# SCH_FARM_2023-08-20.net
KiCad netlist of a schematic drawn in EasyEDA
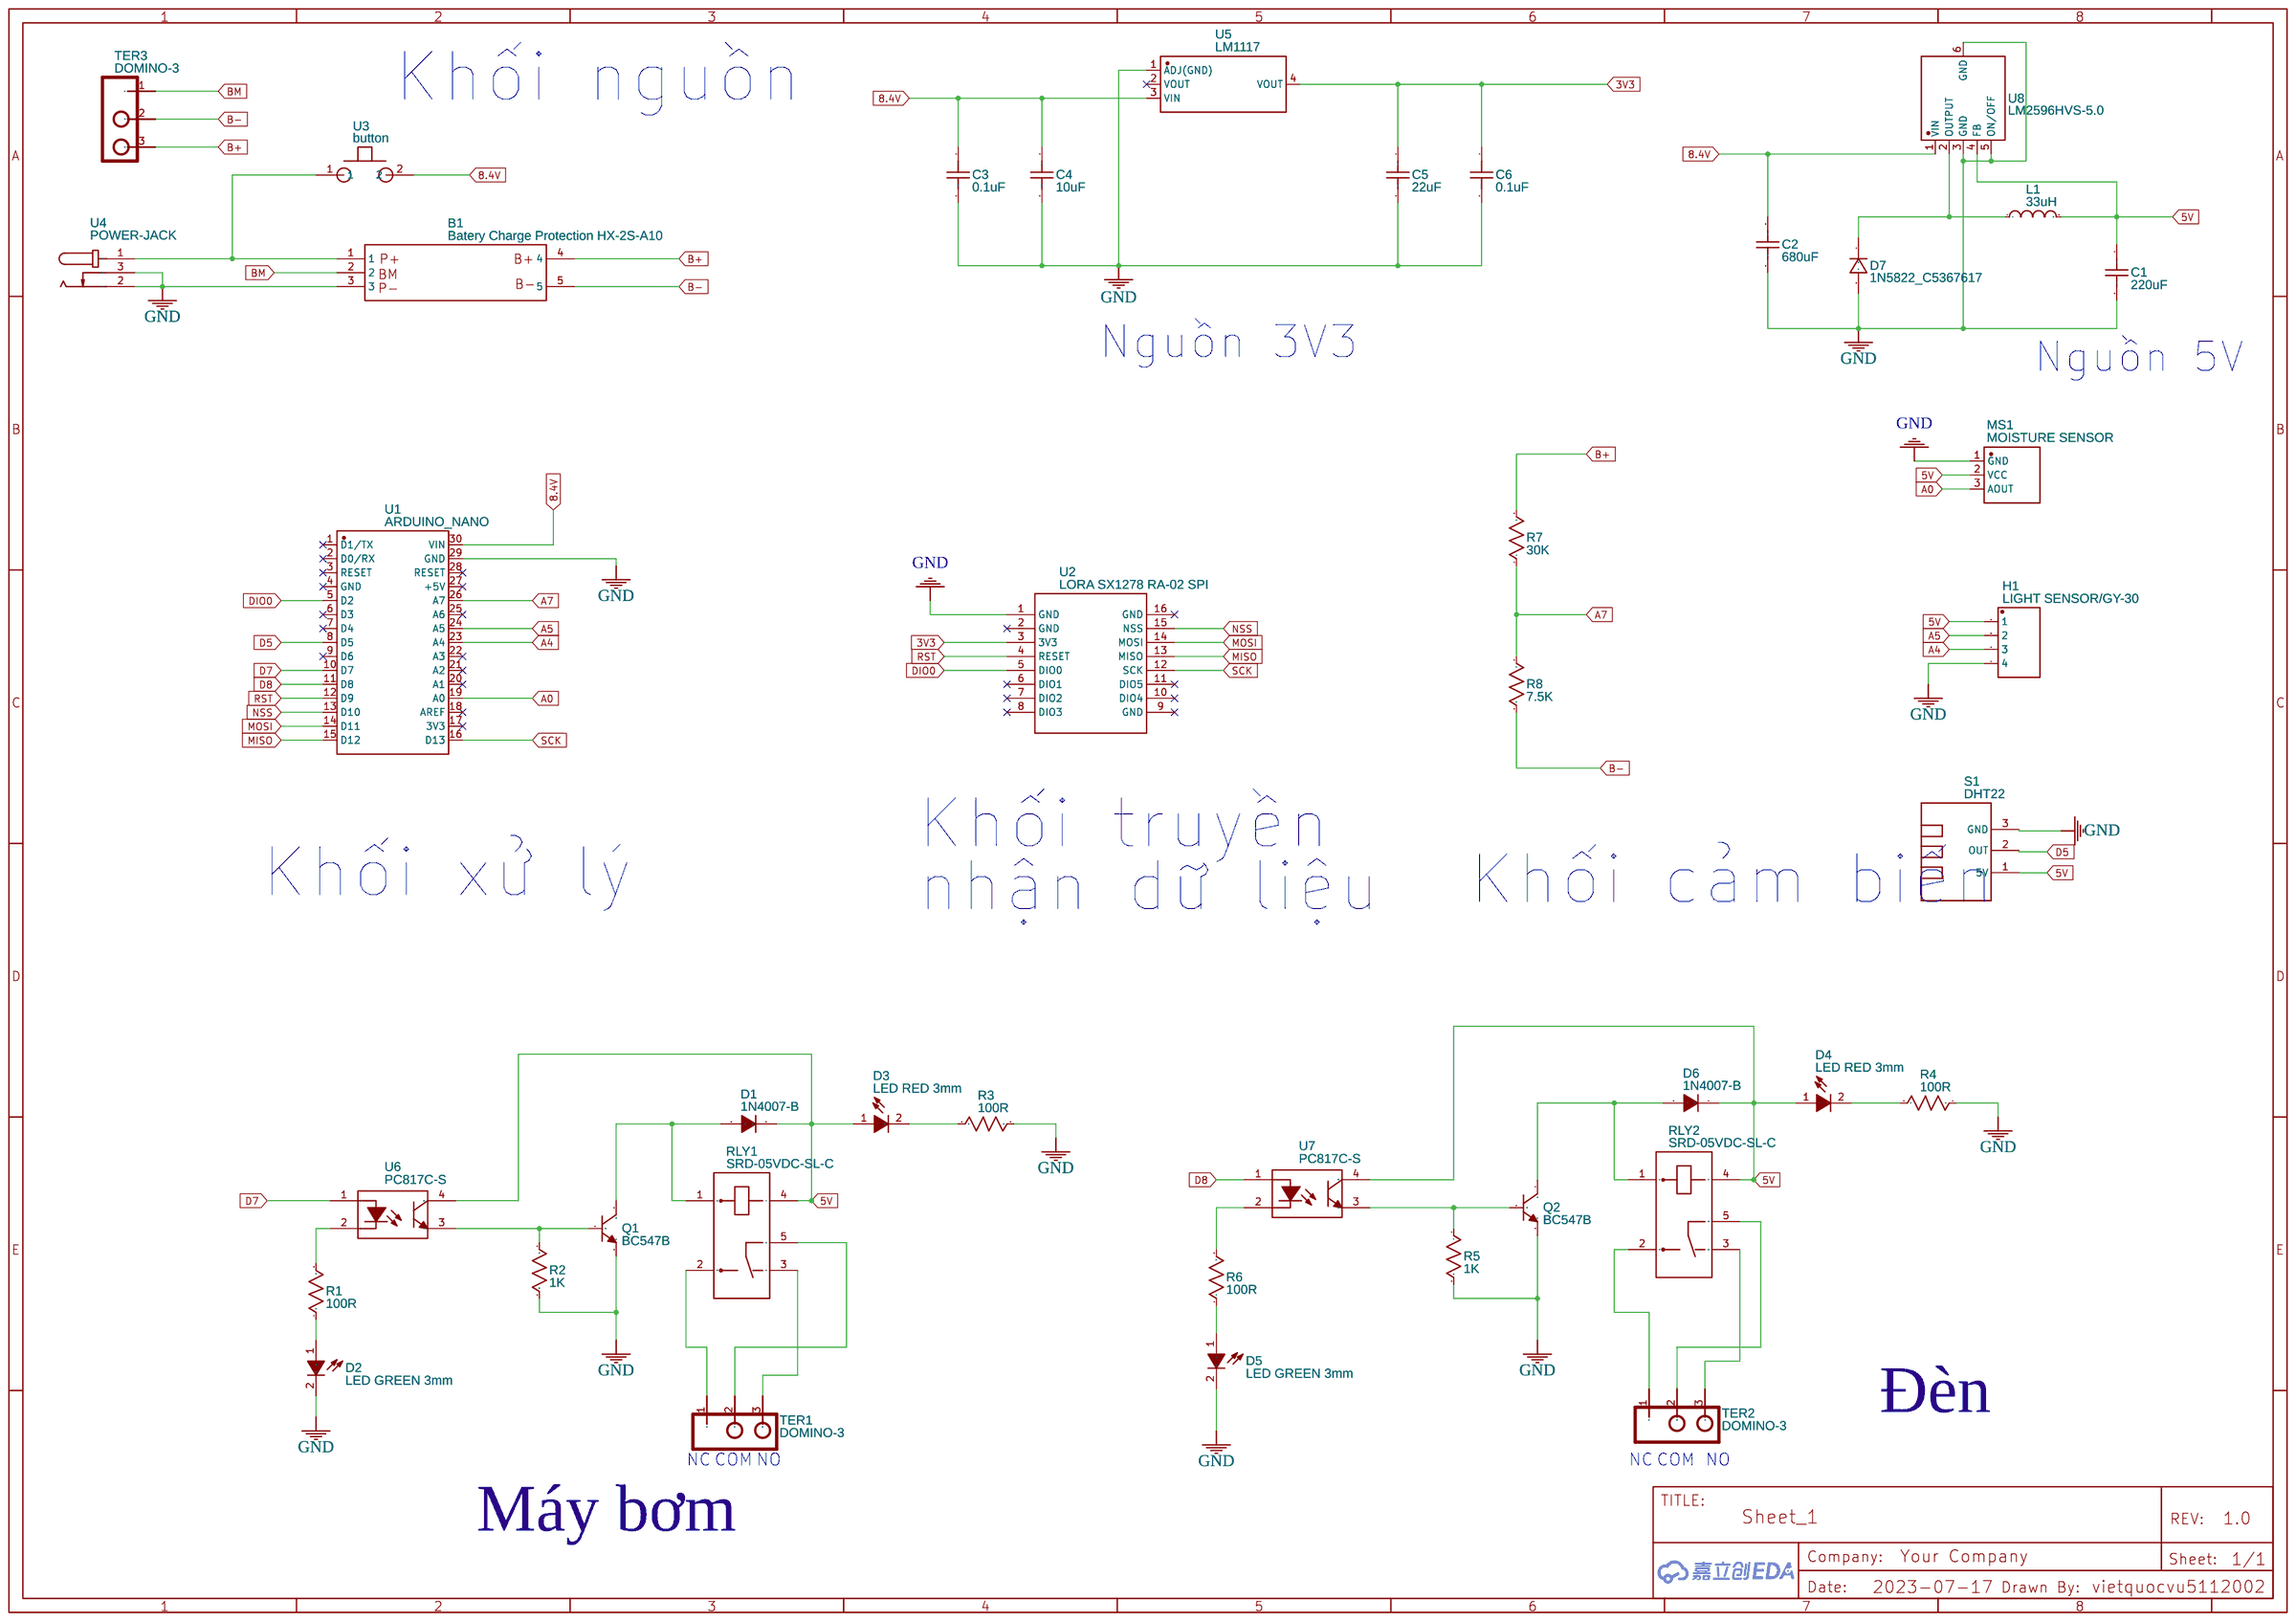
[diagram p0: schematic sheet]

(export (version "E")
  (design (tool "Eeschema 10.0.6"))
  (components
    (comp (ref "B1")
      (value "Batery Charge Protection HX-2S-A10")
      (fields (field (name "BOM_Manufacturer Part") "HX-2S-A10"))
      (libsource (lib "") (part "Batery Charge Protection HX-2S-A10"))
    )
    (comp (ref "C1") (value "220uF") (libsource (lib "") (part "C_0603_US")))
    (comp (ref "C2") (value "680uF") (libsource (lib "") (part "C_0603_US")))
    (comp (ref "C3") (value "0.1uF") (libsource (lib "") (part "C_0603_US")))
    (comp (ref "C4") (value "10uF") (libsource (lib "") (part "C_0603_US")))
    (comp (ref "C5") (value "22uF") (libsource (lib "") (part "C_0603_US")))
    (comp (ref "C6") (value "0.1uF") (libsource (lib "") (part "C_0603_US")))
    (comp (ref "D1")
      (value "1N4007-B")
      (fields (field (name "BOM_Supplier Part") "C526198"))
      (libsource (lib "") (part "1N4007-B"))
    )
    (comp (ref "D2")
      (value "LED GREEN 3mm")
      (fields (field (name "BOM_Manufacturer Part") "5600") (field (name "BOM_Supplier Part") "L20325-ND"))
      (libsource (lib "") (part "3mm Green TH LED 5600_1"))
    )
    (comp (ref "D3")
      (value "LED RED 3mm")
      (fields (field (name "BOM_Manufacturer Part") "5600") (field (name "BOM_Supplier Part") "L20325-ND"))
      (libsource (lib "") (part "3mm Green TH LED 5600"))
    )
    (comp (ref "D4")
      (value "LED RED 3mm")
      (fields (field (name "BOM_Manufacturer Part") "5600") (field (name "BOM_Supplier Part") "L20325-ND"))
      (libsource (lib "") (part "3mm Green TH LED 5600"))
    )
    (comp (ref "D5")
      (value "LED GREEN 3mm")
      (fields (field (name "BOM_Manufacturer Part") "5600") (field (name "BOM_Supplier Part") "L20325-ND"))
      (libsource (lib "") (part "3mm Green TH LED 5600_1"))
    )
    (comp (ref "D6")
      (value "1N4007-B")
      (fields (field (name "BOM_Supplier Part") "C526198"))
      (libsource (lib "") (part "1N4007-B"))
    )
    (comp (ref "D7")
      (value "1N5822_C5367617")
      (fields (field (name "BOM_Manufacturer Part") "1N5822") (field (name "BOM_Supplier Part") "C5367617"))
      (libsource (lib "") (part "1N5822_C5367617"))
    )
    (comp (ref "H1")
      (value "LIGHT SENSOR/GY-30")
      (fields
        (field (name "BOM_Manufacturer Part") "B-2100S04P-A110")
        (field (name "BOM_Supplier Part") "C124378")
      )
      (libsource (lib "") (part "Header-Male-2.54_1x4"))
    )
    (comp (ref "L1") (value "33uH") (libsource (lib "") (part "L0603_US")))
    (comp (ref "MS1") (value "MOISTURE SENSOR") (libsource (lib "") (part "MOISTURE SENSOR")))
    (comp (ref "Q1")
      (value "BC547B")
      (fields (field (name "BOM_Supplier Part") "C713613"))
      (libsource (lib "") (part "BC547B"))
    )
    (comp (ref "Q2")
      (value "BC547B")
      (fields (field (name "BOM_Supplier Part") "C713613"))
      (libsource (lib "") (part "BC547B"))
    )
    (comp (ref "R1") (value "100R") (libsource (lib "") (part "R_0603_US")))
    (comp (ref "R2") (value "1K") (libsource (lib "") (part "R_0603_US_1")))
    (comp (ref "R3") (value "100R") (libsource (lib "") (part "R_0603_US_2")))
    (comp (ref "R4") (value "100R") (libsource (lib "") (part "R_0603_US_2")))
    (comp (ref "R5") (value "1K") (libsource (lib "") (part "R_0603_US_1")))
    (comp (ref "R6") (value "100R") (libsource (lib "") (part "R_0603_US")))
    (comp (ref "R7") (value "30K") (libsource (lib "") (part "R_0603_US")))
    (comp (ref "R8") (value "7.5K") (libsource (lib "") (part "R_0603_US")))
    (comp (ref "RLY1")
      (value "SRD-05VDC-SL-C")
      (fields (field (name "BOM_Supplier Part") "C35449"))
      (libsource (lib "") (part "SRD-05VDC-SL-C"))
    )
    (comp (ref "RLY2")
      (value "SRD-05VDC-SL-C")
      (fields (field (name "BOM_Supplier Part") "C35449"))
      (libsource (lib "") (part "SRD-05VDC-SL-C"))
    )
    (comp (ref "S1") (value "DHT22") (libsource (lib "") (part "DHT22")))
    (comp (ref "TER1") (value "DOMINO-3") (libsource (lib "") (part "DOMINO-3")))
    (comp (ref "TER2") (value "DOMINO-3") (libsource (lib "") (part "DOMINO-3")))
    (comp (ref "TER3") (value "DOMINO-3") (libsource (lib "") (part "DOMINO-3_1")))
    (comp (ref "U1")
      (value "ARDUINO_NANO")
      (fields (field (name "BOM_Supplier Part") "C9900017879"))
      (libsource (lib "") (part "ARDUINO_NANO"))
    )
    (comp (ref "U2") (value "LORA SX1278 RA-02 SPI") (libsource (lib "") (part "LORA SX1278 RA-02 DIP 01")))
    (comp (ref "U3") (value "button") (libsource (lib "") (part "button")))
    (comp (ref "U4")
      (value "POWER-JACK")
      (fields (field (name "BOM_Supplier Part") "C9900001795"))
      (libsource (lib "") (part "POWER-JACK"))
    )
    (comp (ref "U5")
      (value "LM1117")
      (fields
        (field (name "BOM_Manufacturer Part") "AMS1117-ADJ")
        (field (name "BOM_Supplier Part") "C2891840")
      )
      (libsource (lib "") (part "AMS1117-ADJ_C2891840"))
    )
    (comp (ref "U6")
      (value "PC817C-S")
      (fields (field (name "BOM_Supplier Part") "C3008369"))
      (libsource (lib "") (part "PC817C-S"))
    )
    (comp (ref "U7")
      (value "PC817C-S")
      (fields (field (name "BOM_Supplier Part") "C3008369"))
      (libsource (lib "") (part "PC817C-S"))
    )
    (comp (ref "U8")
      (value "LM2596HVS-5.0")
      (fields (field (name "BOM_Supplier Part") "C434497"))
      (libsource (lib "") (part "LM2596HVS-5.0"))
    )
  )
  (nets
    (net (code "1") (name "3V3") (class "Default")
      (node (ref "C5") (pin "1") (pinfunction "1_1") (pintype "unspecified"))
      (node (ref "C6") (pin "1") (pinfunction "1_1") (pintype "unspecified"))
      (node (ref "U2") (pin "3") (pinfunction "3V3_3") (pintype "unspecified"))
      (node (ref "U5") (pin "4") (pinfunction "VOUT_4") (pintype "unspecified"))
    )
    (net (code "2") (name "5V") (class "Default")
      (node (ref "C1") (pin "1") (pinfunction "1_1") (pintype "unspecified"))
      (node (ref "D1") (pin "1") (pinfunction "K_1") (pintype "unspecified"))
      (node (ref "D3") (pin "1") (pinfunction "A_1") (pintype "input"))
      (node (ref "D4") (pin "1") (pinfunction "A_1") (pintype "input"))
      (node (ref "D6") (pin "1") (pinfunction "K_1") (pintype "unspecified"))
      (node (ref "H1") (pin "1") (pinfunction "1_1") (pintype "unspecified"))
      (node (ref "L1") (pin "2") (pinfunction "2_2") (pintype "unspecified"))
      (node (ref "MS1") (pin "2") (pinfunction "VCC_2") (pintype "unspecified"))
      (node (ref "RLY1") (pin "4") (pinfunction "4_4") (pintype "input"))
      (node (ref "RLY2") (pin "4") (pinfunction "4_4") (pintype "input"))
      (node (ref "S1") (pin "1") (pinfunction "5V_1") (pintype "bidirectional"))
      (node (ref "U6") (pin "4") (pinfunction "COL_4") (pintype "unspecified"))
      (node (ref "U7") (pin "4") (pinfunction "COL_4") (pintype "unspecified"))
      (node (ref "U8") (pin "4") (pinfunction "FB_4") (pintype "unspecified"))
    )
    (net (code "3") (name "8.4V") (class "Default")
      (node (ref "C2") (pin "1") (pinfunction "1_1") (pintype "unspecified"))
      (node (ref "C3") (pin "1") (pinfunction "1_1") (pintype "unspecified"))
      (node (ref "C4") (pin "1") (pinfunction "1_1") (pintype "unspecified"))
      (node (ref "U1") (pin "30") (pinfunction "VIN_30") (pintype "unspecified"))
      (node (ref "U3") (pin "2") (pinfunction "2_2") (pintype "unspecified"))
      (node (ref "U5") (pin "3") (pinfunction "VIN_3") (pintype "unspecified"))
      (node (ref "U8") (pin "1") (pinfunction "VIN_1") (pintype "unspecified"))
    )
    (net (code "4") (name "A0") (class "Default")
      (node (ref "MS1") (pin "3") (pinfunction "AOUT_3") (pintype "unspecified"))
      (node (ref "U1") (pin "19") (pinfunction "A0_19") (pintype "unspecified"))
    )
    (net (code "5") (name "A4") (class "Default")
      (node (ref "H1") (pin "3") (pinfunction "3_3") (pintype "unspecified"))
      (node (ref "U1") (pin "23") (pinfunction "A4_23") (pintype "unspecified"))
    )
    (net (code "6") (name "A5") (class "Default")
      (node (ref "H1") (pin "2") (pinfunction "2_2") (pintype "unspecified"))
      (node (ref "U1") (pin "24") (pinfunction "A5_24") (pintype "unspecified"))
    )
    (net (code "7") (name "A7") (class "Default")
      (node (ref "R7") (pin "1") (pinfunction "1_1") (pintype "unspecified"))
      (node (ref "R8") (pin "2") (pinfunction "2_2") (pintype "unspecified"))
      (node (ref "U1") (pin "26") (pinfunction "A7_26") (pintype "unspecified"))
    )
    (net (code "8") (name "B+") (class "Default")
      (node (ref "B1") (pin "4") (pinfunction "4_4") (pintype "unspecified"))
      (node (ref "R7") (pin "2") (pinfunction "2_2") (pintype "unspecified"))
      (node (ref "TER3") (pin "3") (pinfunction "3_3") (pintype "bidirectional"))
    )
    (net (code "9") (name "B-") (class "Default")
      (node (ref "B1") (pin "5") (pinfunction "5_5") (pintype "unspecified"))
      (node (ref "R8") (pin "1") (pinfunction "1_1") (pintype "unspecified"))
      (node (ref "TER3") (pin "2") (pinfunction "2_2") (pintype "bidirectional"))
    )
    (net (code "10") (name "BM") (class "Default")
      (node (ref "B1") (pin "2") (pinfunction "2_2") (pintype "unspecified"))
      (node (ref "TER3") (pin "1") (pinfunction "1_1") (pintype "bidirectional"))
    )
    (net (code "11") (name "D5") (class "Default")
      (node (ref "S1") (pin "2") (pinfunction "OUT_2") (pintype "bidirectional"))
      (node (ref "U1") (pin "8") (pinfunction "D5_8") (pintype "unspecified"))
    )
    (net (code "12") (name "D7") (class "Default")
      (node (ref "U1") (pin "10") (pinfunction "D7_10") (pintype "unspecified"))
      (node (ref "U6") (pin "1") (pinfunction "AN_1") (pintype "unspecified"))
    )
    (net (code "13") (name "D8") (class "Default")
      (node (ref "U1") (pin "11") (pinfunction "D8_11") (pintype "unspecified"))
      (node (ref "U7") (pin "1") (pinfunction "AN_1") (pintype "unspecified"))
    )
    (net (code "14") (name "DIO0") (class "Default")
      (node (ref "U1") (pin "5") (pinfunction "D2_5") (pintype "unspecified"))
      (node (ref "U2") (pin "5") (pinfunction "DIO0_5") (pintype "unspecified"))
    )
    (net (code "15") (name "GND") (class "Default")
      (node (ref "B1") (pin "3") (pinfunction "3_3") (pintype "unspecified"))
      (node (ref "C1") (pin "2") (pinfunction "2_2") (pintype "unspecified"))
      (node (ref "C2") (pin "2") (pinfunction "2_2") (pintype "unspecified"))
      (node (ref "C3") (pin "2") (pinfunction "2_2") (pintype "unspecified"))
      (node (ref "C4") (pin "2") (pinfunction "2_2") (pintype "unspecified"))
      (node (ref "C5") (pin "2") (pinfunction "2_2") (pintype "unspecified"))
      (node (ref "C6") (pin "2") (pinfunction "2_2") (pintype "unspecified"))
      (node (ref "D2") (pin "2") (pinfunction "K_2") (pintype "input"))
      (node (ref "D5") (pin "2") (pinfunction "K_2") (pintype "input"))
      (node (ref "D7") (pin "2") (pinfunction "A_2") (pintype "unspecified"))
      (node (ref "H1") (pin "4") (pinfunction "4_4") (pintype "unspecified"))
      (node (ref "MS1") (pin "1") (pinfunction "GND_1") (pintype "unspecified"))
      (node (ref "Q1") (pin "3") (pinfunction "E_3") (pintype "input"))
      (node (ref "Q2") (pin "3") (pinfunction "E_3") (pintype "input"))
      (node (ref "R2") (pin "2") (pinfunction "2_2") (pintype "unspecified"))
      (node (ref "R3") (pin "1") (pinfunction "1_1") (pintype "unspecified"))
      (node (ref "R4") (pin "1") (pinfunction "1_1") (pintype "unspecified"))
      (node (ref "R5") (pin "2") (pinfunction "2_2") (pintype "unspecified"))
      (node (ref "S1") (pin "3") (pinfunction "GND_3") (pintype "bidirectional"))
      (node (ref "U1") (pin "29") (pinfunction "GND_29") (pintype "unspecified"))
      (node (ref "U2") (pin "1") (pinfunction "GND_1") (pintype "unspecified"))
      (node (ref "U4") (pin "2") (pinfunction "2_2") (pintype "unspecified"))
      (node (ref "U4") (pin "3") (pinfunction "3_3") (pintype "unspecified"))
      (node (ref "U5") (pin "1") (pinfunction "ADJ(GND)_1") (pintype "unspecified"))
      (node (ref "U8") (pin "3") (pinfunction "GND_3") (pintype "unspecified"))
      (node (ref "U8") (pin "5") (pinfunction "ON/OFF_5") (pintype "unspecified"))
      (node (ref "U8") (pin "6") (pinfunction "GND_6") (pintype "unspecified"))
    )
    (net (code "16") (name "MISO") (class "Default")
      (node (ref "U1") (pin "15") (pinfunction "D12_15") (pintype "unspecified"))
      (node (ref "U2") (pin "13") (pinfunction "MISO_13") (pintype "unspecified"))
    )
    (net (code "17") (name "MOSI") (class "Default")
      (node (ref "U1") (pin "14") (pinfunction "D11_14") (pintype "unspecified"))
      (node (ref "U2") (pin "14") (pinfunction "MOSI_14") (pintype "unspecified"))
    )
    (net (code "18") (name "NSS") (class "Default")
      (node (ref "U1") (pin "13") (pinfunction "D10_13") (pintype "unspecified"))
      (node (ref "U2") (pin "15") (pinfunction "NSS_15") (pintype "unspecified"))
    )
    (net (code "19") (name "Net-(B1-Pad1)") (class "Default")
      (node (ref "B1") (pin "1") (pinfunction "1_1") (pintype "unspecified"))
      (node (ref "U3") (pin "1") (pinfunction "1_1") (pintype "unspecified"))
      (node (ref "U4") (pin "1") (pinfunction "1_1") (pintype "unspecified"))
    )
    (net (code "20") (name "Net-(D1-A)") (class "Default")
      (node (ref "D1") (pin "2") (pinfunction "A_2") (pintype "unspecified"))
      (node (ref "Q1") (pin "1") (pinfunction "C_1") (pintype "input"))
      (node (ref "RLY1") (pin "1") (pinfunction "1_1") (pintype "input"))
    )
    (net (code "21") (name "Net-(D2-A)") (class "Default")
      (node (ref "D2") (pin "1") (pinfunction "A_1") (pintype "input"))
      (node (ref "R1") (pin "1") (pinfunction "1_1") (pintype "unspecified"))
    )
    (net (code "22") (name "Net-(D3-K)") (class "Default")
      (node (ref "D3") (pin "2") (pinfunction "K_2") (pintype "input"))
      (node (ref "R3") (pin "2") (pinfunction "2_2") (pintype "unspecified"))
    )
    (net (code "23") (name "Net-(D4-K)") (class "Default")
      (node (ref "D4") (pin "2") (pinfunction "K_2") (pintype "input"))
      (node (ref "R4") (pin "2") (pinfunction "2_2") (pintype "unspecified"))
    )
    (net (code "24") (name "Net-(D5-A)") (class "Default")
      (node (ref "D5") (pin "1") (pinfunction "A_1") (pintype "input"))
      (node (ref "R6") (pin "1") (pinfunction "1_1") (pintype "unspecified"))
    )
    (net (code "25") (name "Net-(D6-A)") (class "Default")
      (node (ref "D6") (pin "2") (pinfunction "A_2") (pintype "unspecified"))
      (node (ref "Q2") (pin "1") (pinfunction "C_1") (pintype "input"))
      (node (ref "RLY2") (pin "1") (pinfunction "1_1") (pintype "input"))
    )
    (net (code "26") (name "Net-(D7-C)") (class "Default")
      (node (ref "D7") (pin "1") (pinfunction "C_1") (pintype "unspecified"))
      (node (ref "L1") (pin "1") (pinfunction "1_1") (pintype "unspecified"))
      (node (ref "U8") (pin "2") (pinfunction "OUTPUT_2") (pintype "unspecified"))
    )
    (net (code "27") (name "Net-(Q1-B)") (class "Default")
      (node (ref "Q1") (pin "2") (pinfunction "B_2") (pintype "input"))
      (node (ref "R2") (pin "1") (pinfunction "1_1") (pintype "unspecified"))
      (node (ref "U6") (pin "3") (pinfunction "EM_3") (pintype "unspecified"))
    )
    (net (code "28") (name "Net-(Q2-B)") (class "Default")
      (node (ref "Q2") (pin "2") (pinfunction "B_2") (pintype "input"))
      (node (ref "R5") (pin "1") (pinfunction "1_1") (pintype "unspecified"))
      (node (ref "U7") (pin "3") (pinfunction "EM_3") (pintype "unspecified"))
    )
    (net (code "29") (name "Net-(RLY1-Pad2)") (class "Default")
      (node (ref "RLY1") (pin "2") (pinfunction "2_2") (pintype "input"))
      (node (ref "TER1") (pin "1") (pinfunction "1_1") (pintype "bidirectional"))
    )
    (net (code "30") (name "Net-(RLY1-Pad3)") (class "Default")
      (node (ref "RLY1") (pin "3") (pinfunction "3_3") (pintype "input"))
      (node (ref "TER1") (pin "3") (pinfunction "3_3") (pintype "bidirectional"))
    )
    (net (code "31") (name "Net-(RLY1-Pad5)") (class "Default")
      (node (ref "RLY1") (pin "5") (pinfunction "5_5") (pintype "input"))
      (node (ref "TER1") (pin "2") (pinfunction "2_2") (pintype "bidirectional"))
    )
    (net (code "32") (name "Net-(RLY2-Pad2)") (class "Default")
      (node (ref "RLY2") (pin "2") (pinfunction "2_2") (pintype "input"))
      (node (ref "TER2") (pin "1") (pinfunction "1_1") (pintype "bidirectional"))
    )
    (net (code "33") (name "Net-(RLY2-Pad3)") (class "Default")
      (node (ref "RLY2") (pin "3") (pinfunction "3_3") (pintype "input"))
      (node (ref "TER2") (pin "3") (pinfunction "3_3") (pintype "bidirectional"))
    )
    (net (code "34") (name "Net-(RLY2-Pad5)") (class "Default")
      (node (ref "RLY2") (pin "5") (pinfunction "5_5") (pintype "input"))
      (node (ref "TER2") (pin "2") (pinfunction "2_2") (pintype "bidirectional"))
    )
    (net (code "35") (name "Net-(U6-CAT)") (class "Default")
      (node (ref "R1") (pin "2") (pinfunction "2_2") (pintype "unspecified"))
      (node (ref "U6") (pin "2") (pinfunction "CAT_2") (pintype "unspecified"))
    )
    (net (code "36") (name "Net-(U7-CAT)") (class "Default")
      (node (ref "R6") (pin "2") (pinfunction "2_2") (pintype "unspecified"))
      (node (ref "U7") (pin "2") (pinfunction "CAT_2") (pintype "unspecified"))
    )
    (net (code "37") (name "RST") (class "Default")
      (node (ref "U1") (pin "12") (pinfunction "D9_12") (pintype "unspecified"))
      (node (ref "U2") (pin "4") (pinfunction "RESET_4") (pintype "unspecified"))
    )
    (net (code "38") (name "SCK") (class "Default")
      (node (ref "U1") (pin "16") (pinfunction "D13_16") (pintype "unspecified"))
      (node (ref "U2") (pin "12") (pinfunction "SCK_12") (pintype "unspecified"))
    )
    (net (code "39") (name "unconnected-(U1-+5V-Pad27)") (class "Default")
      (node (ref "U1") (pin "27") (pinfunction "+5V_27") (pintype "unspecified+no_connect"))
    )
    (net (code "40") (name "unconnected-(U1-3V3-Pad17)") (class "Default")
      (node (ref "U1") (pin "17") (pinfunction "3V3_17") (pintype "unspecified+no_connect"))
    )
    (net (code "41") (name "unconnected-(U1-A1-Pad20)") (class "Default")
      (node (ref "U1") (pin "20") (pinfunction "A1_20") (pintype "unspecified+no_connect"))
    )
    (net (code "42") (name "unconnected-(U1-A2-Pad21)") (class "Default")
      (node (ref "U1") (pin "21") (pinfunction "A2_21") (pintype "unspecified+no_connect"))
    )
    (net (code "43") (name "unconnected-(U1-A3-Pad22)") (class "Default")
      (node (ref "U1") (pin "22") (pinfunction "A3_22") (pintype "unspecified+no_connect"))
    )
    (net (code "44") (name "unconnected-(U1-A6-Pad25)") (class "Default")
      (node (ref "U1") (pin "25") (pinfunction "A6_25") (pintype "unspecified+no_connect"))
    )
    (net (code "45") (name "unconnected-(U1-AREF-Pad18)") (class "Default")
      (node (ref "U1") (pin "18") (pinfunction "AREF_18") (pintype "unspecified+no_connect"))
    )
    (net (code "46") (name "unconnected-(U1-D0{slash}RX-Pad2)") (class "Default")
      (node (ref "U1") (pin "2") (pinfunction "D0/RX_2") (pintype "unspecified+no_connect"))
    )
    (net (code "47") (name "unconnected-(U1-D1{slash}TX-Pad1)") (class "Default")
      (node (ref "U1") (pin "1") (pinfunction "D1/TX_1") (pintype "unspecified+no_connect"))
    )
    (net (code "48") (name "unconnected-(U1-D3-Pad6)") (class "Default")
      (node (ref "U1") (pin "6") (pinfunction "D3_6") (pintype "unspecified+no_connect"))
    )
    (net (code "49") (name "unconnected-(U1-D4-Pad7)") (class "Default")
      (node (ref "U1") (pin "7") (pinfunction "D4_7") (pintype "unspecified+no_connect"))
    )
    (net (code "50") (name "unconnected-(U1-D6-Pad9)") (class "Default")
      (node (ref "U1") (pin "9") (pinfunction "D6_9") (pintype "unspecified+no_connect"))
    )
    (net (code "51") (name "unconnected-(U1-GND-Pad4)") (class "Default")
      (node (ref "U1") (pin "4") (pinfunction "GND_4") (pintype "unspecified+no_connect"))
    )
    (net (code "52") (name "unconnected-(U1-RESET-Pad3)") (class "Default")
      (node (ref "U1") (pin "3") (pinfunction "RESET_3") (pintype "unspecified+no_connect"))
    )
    (net (code "53") (name "unconnected-(U1-RESET-Pad28)") (class "Default")
      (node (ref "U1") (pin "28") (pinfunction "RESET_28") (pintype "unspecified+no_connect"))
    )
    (net (code "54") (name "unconnected-(U2-DIO1-Pad6)") (class "Default")
      (node (ref "U2") (pin "6") (pinfunction "DIO1_6") (pintype "unspecified+no_connect"))
    )
    (net (code "55") (name "unconnected-(U2-DIO2-Pad7)") (class "Default")
      (node (ref "U2") (pin "7") (pinfunction "DIO2_7") (pintype "unspecified+no_connect"))
    )
    (net (code "56") (name "unconnected-(U2-DIO3-Pad8)") (class "Default")
      (node (ref "U2") (pin "8") (pinfunction "DIO3_8") (pintype "unspecified+no_connect"))
    )
    (net (code "57") (name "unconnected-(U2-DIO4-Pad10)") (class "Default")
      (node (ref "U2") (pin "10") (pinfunction "DIO4_10") (pintype "unspecified+no_connect"))
    )
    (net (code "58") (name "unconnected-(U2-DIO5-Pad11)") (class "Default")
      (node (ref "U2") (pin "11") (pinfunction "DIO5_11") (pintype "unspecified+no_connect"))
    )
    (net (code "59") (name "unconnected-(U2-GND-Pad2)") (class "Default")
      (node (ref "U2") (pin "2") (pinfunction "GND_2") (pintype "unspecified+no_connect"))
    )
    (net (code "60") (name "unconnected-(U2-GND-Pad9)") (class "Default")
      (node (ref "U2") (pin "9") (pinfunction "GND_9") (pintype "unspecified+no_connect"))
    )
    (net (code "61") (name "unconnected-(U2-GND-Pad16)") (class "Default")
      (node (ref "U2") (pin "16") (pinfunction "GND_16") (pintype "unspecified+no_connect"))
    )
    (net (code "62") (name "unconnected-(U5-VOUT-Pad2)") (class "Default")
      (node (ref "U5") (pin "2") (pinfunction "VOUT_2") (pintype "unspecified+no_connect"))
    )
  )
)
